# keyboard.net
KiCad netlist of a schematic drawn in EAGLE
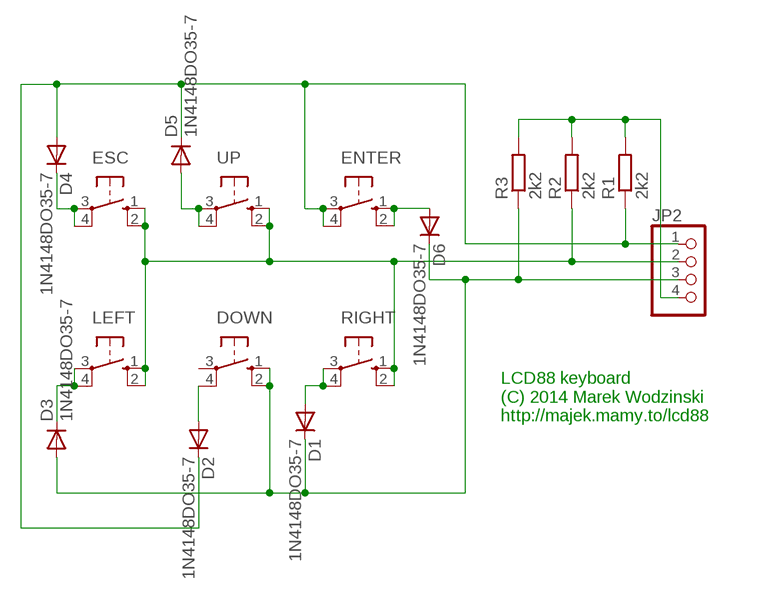
[diagram p0: schematic, sheet 1]

(export (version "E")
  (design (tool "Eeschema 10.0.6"))
  (components
    (comp (ref "D1")
      (value "1N4148DO35-7")
      (footprint "eagle-import:DO35-7")
      (libsource (lib "eagle-import") (part "1N4148DO35-7"))
    )
    (comp (ref "D2")
      (value "1N4148DO35-7")
      (footprint "eagle-import:DO35-7")
      (libsource (lib "eagle-import") (part "1N4148DO35-7"))
    )
    (comp (ref "D3")
      (value "1N4148DO35-7")
      (footprint "eagle-import:DO35-7")
      (libsource (lib "eagle-import") (part "1N4148DO35-7"))
    )
    (comp (ref "D4")
      (value "1N4148DO35-7")
      (footprint "eagle-import:DO35-7")
      (libsource (lib "eagle-import") (part "1N4148DO35-7"))
    )
    (comp (ref "D5")
      (value "1N4148DO35-7")
      (footprint "eagle-import:DO35-7")
      (libsource (lib "eagle-import") (part "1N4148DO35-7"))
    )
    (comp (ref "D6")
      (value "1N4148DO35-7")
      (footprint "eagle-import:DO35-7")
      (libsource (lib "eagle-import") (part "1N4148DO35-7"))
    )
    (comp (ref "DOWN")
      (value "10-XX")
      (footprint "eagle-import:B3F-10XX")
      (libsource (lib "eagle-import") (part "10-XX"))
    )
    (comp (ref "ENTER")
      (value "10-XX")
      (footprint "eagle-import:B3F-10XX")
      (libsource (lib "eagle-import") (part "10-XX"))
    )
    (comp (ref "ESC")
      (value "10-XX")
      (footprint "eagle-import:B3F-10XX")
      (libsource (lib "eagle-import") (part "10-XX"))
    )
    (comp (ref "JP2")
      (value "PINHD-1X4")
      (footprint "eagle-import:1X04")
      (libsource (lib "eagle-import") (part "PINHD-1X4"))
    )
    (comp (ref "LEFT")
      (value "10-XX")
      (footprint "eagle-import:B3F-10XX")
      (libsource (lib "eagle-import") (part "10-XX"))
    )
    (comp (ref "R1")
      (value "2k2")
      (footprint "eagle-import:R0805W")
      (libsource (lib "eagle-import") (part "R-EU_R0805W"))
    )
    (comp (ref "R2")
      (value "2k2")
      (footprint "eagle-import:R0805W")
      (libsource (lib "eagle-import") (part "R-EU_R0805W"))
    )
    (comp (ref "R3")
      (value "2k2")
      (footprint "eagle-import:R0805W")
      (libsource (lib "eagle-import") (part "R-EU_R0805W"))
    )
    (comp (ref "RIGHT")
      (value "10-XX")
      (footprint "eagle-import:B3F-10XX")
      (libsource (lib "eagle-import") (part "10-XX"))
    )
    (comp (ref "UP")
      (value "10-XX")
      (footprint "eagle-import:B3F-10XX")
      (libsource (lib "eagle-import") (part "10-XX"))
    )
  )
  (nets
    (net (code "1") (name "Net-(DOWN-P1)") (class "Default")
      (node (ref "D2") (pin "A") (pinfunction "A_A") (pintype "passive"))
      (node (ref "DOWN") (pin "4") (pinfunction "P1_4") (pintype "passive"))
    )
    (net (code "2") (name "Net-(DOWN-S)") (class "Default")
      (node (ref "D1") (pin "C") (pinfunction "C_C") (pintype "passive"))
      (node (ref "D3") (pin "A") (pinfunction "A_A") (pintype "passive"))
      (node (ref "D6") (pin "C") (pinfunction "C_C") (pintype "passive"))
      (node (ref "DOWN") (pin "1") (pinfunction "S_1") (pintype "passive"))
      (node (ref "DOWN") (pin "2") (pinfunction "S1_2") (pintype "passive"))
      (node (ref "JP2") (pin "3") (pinfunction "3_3") (pintype "passive"))
      (node (ref "R3") (pin "1") (pinfunction "1_1") (pintype "passive"))
    )
    (net (code "3") (name "Net-(ENTER-P)") (class "Default")
      (node (ref "D2") (pin "C") (pinfunction "C_C") (pintype "passive"))
      (node (ref "D4") (pin "A") (pinfunction "A_A") (pintype "passive"))
      (node (ref "D5") (pin "C") (pinfunction "C_C") (pintype "passive"))
      (node (ref "ENTER") (pin "3") (pinfunction "P_3") (pintype "passive"))
      (node (ref "ENTER") (pin "4") (pinfunction "P1_4") (pintype "passive"))
      (node (ref "JP2") (pin "1") (pinfunction "1_1") (pintype "passive"))
      (node (ref "R1") (pin "1") (pinfunction "1_1") (pintype "passive"))
    )
    (net (code "4") (name "Net-(ENTER-S)") (class "Default")
      (node (ref "D6") (pin "A") (pinfunction "A_A") (pintype "passive"))
      (node (ref "ENTER") (pin "1") (pinfunction "S_1") (pintype "passive"))
      (node (ref "ENTER") (pin "2") (pinfunction "S1_2") (pintype "passive"))
    )
    (net (code "5") (name "Net-(ESC-P)") (class "Default")
      (node (ref "D4") (pin "C") (pinfunction "C_C") (pintype "passive"))
      (node (ref "ESC") (pin "3") (pinfunction "P_3") (pintype "passive"))
      (node (ref "ESC") (pin "4") (pinfunction "P1_4") (pintype "passive"))
    )
    (net (code "6") (name "Net-(ESC-S)") (class "Default")
      (node (ref "ESC") (pin "1") (pinfunction "S_1") (pintype "passive"))
      (node (ref "ESC") (pin "2") (pinfunction "S1_2") (pintype "passive"))
      (node (ref "JP2") (pin "2") (pinfunction "2_2") (pintype "passive"))
      (node (ref "LEFT") (pin "1") (pinfunction "S_1") (pintype "passive"))
      (node (ref "LEFT") (pin "2") (pinfunction "S1_2") (pintype "passive"))
      (node (ref "R2") (pin "1") (pinfunction "1_1") (pintype "passive"))
      (node (ref "RIGHT") (pin "1") (pinfunction "S_1") (pintype "passive"))
      (node (ref "RIGHT") (pin "2") (pinfunction "S1_2") (pintype "passive"))
      (node (ref "UP") (pin "1") (pinfunction "S_1") (pintype "passive"))
      (node (ref "UP") (pin "2") (pinfunction "S1_2") (pintype "passive"))
    )
    (net (code "7") (name "Net-(JP2-Pad4)") (class "Default")
      (node (ref "JP2") (pin "4") (pinfunction "4_4") (pintype "passive"))
      (node (ref "R1") (pin "2") (pinfunction "2_2") (pintype "passive"))
      (node (ref "R2") (pin "2") (pinfunction "2_2") (pintype "passive"))
      (node (ref "R3") (pin "2") (pinfunction "2_2") (pintype "passive"))
    )
    (net (code "8") (name "Net-(LEFT-P)") (class "Default")
      (node (ref "D3") (pin "C") (pinfunction "C_C") (pintype "passive"))
      (node (ref "LEFT") (pin "3") (pinfunction "P_3") (pintype "passive"))
      (node (ref "LEFT") (pin "4") (pinfunction "P1_4") (pintype "passive"))
    )
    (net (code "9") (name "Net-(RIGHT-P)") (class "Default")
      (node (ref "D1") (pin "A") (pinfunction "A_A") (pintype "passive"))
      (node (ref "RIGHT") (pin "3") (pinfunction "P_3") (pintype "passive"))
      (node (ref "RIGHT") (pin "4") (pinfunction "P1_4") (pintype "passive"))
    )
    (net (code "10") (name "Net-(UP-P)") (class "Default")
      (node (ref "D5") (pin "A") (pinfunction "A_A") (pintype "passive"))
      (node (ref "UP") (pin "3") (pinfunction "P_3") (pintype "passive"))
      (node (ref "UP") (pin "4") (pinfunction "P1_4") (pintype "passive"))
    )
    (net (code "11") (name "unconnected-(DOWN-P-Pad3)") (class "Default")
      (node (ref "DOWN") (pin "3") (pinfunction "P_3") (pintype "passive"))
    )
  )
)
